# badgeSchem.net
KiCad netlist of a schematic drawn in EAGLE
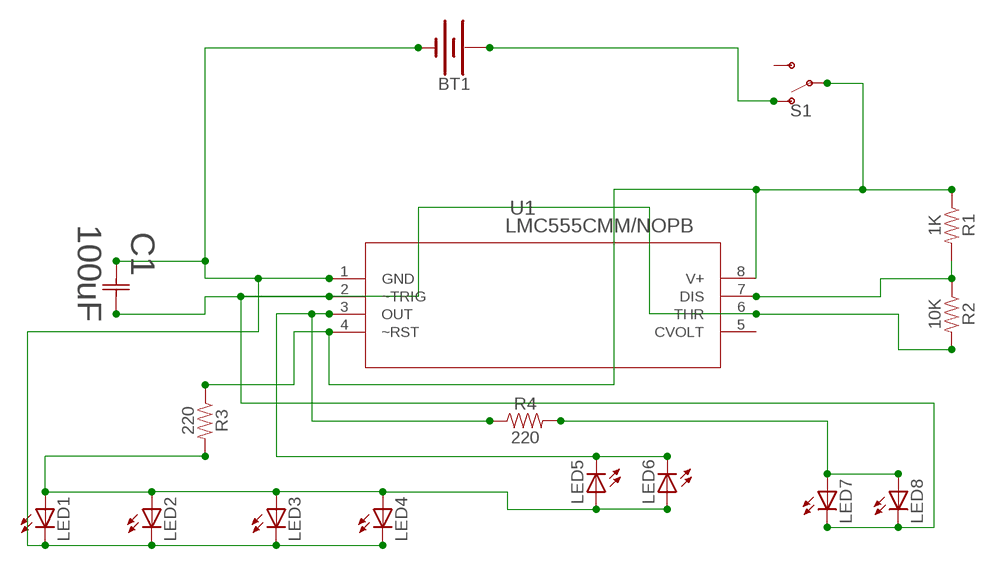
[diagram p0: schematic, sheet 1]

(export (version "E")
  (design (tool "Eeschema 10.0.6"))
  (components
    (comp (ref "BT1")
      (value "BATTERY-12MM_PTH")
      (footprint "eagle-import:BATTCON_12MM_PTH")
      (libsource (lib "eagle-import") (part "BATTERY-12MM_PTH"))
    )
    (comp (ref "C1")
      (value "100uF")
      (footprint "eagle-import:CAP_2012-M")
      (fields (field (name "MANUFACTURER_PART_NUMBER") "C2012C0G1H103J060AA"))
      (libsource (lib "eagle-import") (part "C2012C0G1H103J060AACAP_2012-M"))
    )
    (comp (ref "LED1")
      (value "LEDSML0805")
      (footprint "eagle-import:SML0805")
      (libsource (lib "eagle-import") (part "LEDSML0805"))
    )
    (comp (ref "LED2")
      (value "LEDSML0805")
      (footprint "eagle-import:SML0805")
      (libsource (lib "eagle-import") (part "LEDSML0805"))
    )
    (comp (ref "LED3")
      (value "LEDSML0805")
      (footprint "eagle-import:SML0805")
      (libsource (lib "eagle-import") (part "LEDSML0805"))
    )
    (comp (ref "LED4")
      (value "LEDSML0805")
      (footprint "eagle-import:SML0805")
      (libsource (lib "eagle-import") (part "LEDSML0805"))
    )
    (comp (ref "LED5")
      (value "LEDSML0805")
      (footprint "eagle-import:SML0805")
      (libsource (lib "eagle-import") (part "LEDSML0805"))
    )
    (comp (ref "LED6")
      (value "LEDSML0805")
      (footprint "eagle-import:SML0805")
      (libsource (lib "eagle-import") (part "LEDSML0805"))
    )
    (comp (ref "LED7")
      (value "LEDSML0805")
      (footprint "eagle-import:SML0805")
      (libsource (lib "eagle-import") (part "LEDSML0805"))
    )
    (comp (ref "LED8")
      (value "LEDSML0805")
      (footprint "eagle-import:SML0805")
      (libsource (lib "eagle-import") (part "LEDSML0805"))
    )
    (comp (ref "R1")
      (value "1K")
      (footprint "eagle-import:0805")
      (libsource (lib "eagle-import") (part "0.3OHM-0805-1/8W-1%"))
    )
    (comp (ref "R2")
      (value "10K")
      (footprint "eagle-import:0805")
      (libsource (lib "eagle-import") (part "0.3OHM-0805-1/8W-1%"))
    )
    (comp (ref "R3")
      (value "220")
      (footprint "eagle-import:0805")
      (libsource (lib "eagle-import") (part "0.3OHM-0805-1/8W-1%"))
    )
    (comp (ref "R4")
      (value "220")
      (footprint "eagle-import:0805")
      (libsource (lib "eagle-import") (part "0.3OHM-0805-1/8W-1%"))
    )
    (comp (ref "S1")
      (value "SWITCH-SPDT-SMD-RIGHT-ANGLE")
      (footprint "eagle-import:SWITCH_SPST_SMD_A")
      (libsource (lib "eagle-import") (part "SWITCH-SPDT-SMD-RIGHT-ANGLE"))
    )
    (comp (ref "U1")
      (value "LMC555CMM/NOPB")
      (footprint "eagle-import:MUA08A")
      (fields (field (name "MANUFACTURER_PART_NUMBER") "LMC555CMMNOPB"))
      (libsource (lib "eagle-import") (part "LMC555CMM/NOPB"))
    )
  )
  (nets
    (net (code "1") (name "Net-(BT1-+)") (class "Default")
      (node (ref "BT1") (pin "VCC@1") (pinfunction "+_VCC@1") (pintype "power_in"))
      (node (ref "S1") (pin "1") (pinfunction "O_1") (pintype "passive"))
    )
    (net (code "2") (name "Net-(BT1--)") (class "Default")
      (node (ref "BT1") (pin "GND") (pinfunction "-_GND") (pintype "power_in"))
      (node (ref "C1") (pin "1") (pinfunction "11_1") (pintype "passive"))
      (node (ref "LED1") (pin "C") (pinfunction "C_C") (pintype "passive"))
      (node (ref "LED2") (pin "C") (pinfunction "C_C") (pintype "passive"))
      (node (ref "LED3") (pin "C") (pinfunction "C_C") (pintype "passive"))
      (node (ref "LED4") (pin "C") (pinfunction "C_C") (pintype "passive"))
      (node (ref "U1") (pin "1") (pinfunction "GND_1") (pintype "power_in"))
    )
    (net (code "3") (name "Net-(C1-22)") (class "Default")
      (node (ref "C1") (pin "2") (pinfunction "22_2") (pintype "passive"))
      (node (ref "LED7") (pin "C") (pinfunction "C_C") (pintype "passive"))
      (node (ref "LED8") (pin "C") (pinfunction "C_C") (pintype "passive"))
      (node (ref "R2") (pin "2") (pinfunction "2_2") (pintype "passive"))
      (node (ref "U1") (pin "2") (pinfunction "~{TRIG}_2") (pintype "input"))
      (node (ref "U1") (pin "6") (pinfunction "THR_6") (pintype "input"))
    )
    (net (code "4") (name "Net-(LED1-PadA)") (class "Default")
      (node (ref "LED1") (pin "A") (pinfunction "A_A") (pintype "passive"))
      (node (ref "LED2") (pin "A") (pinfunction "A_A") (pintype "passive"))
      (node (ref "LED3") (pin "A") (pinfunction "A_A") (pintype "passive"))
      (node (ref "LED4") (pin "A") (pinfunction "A_A") (pintype "passive"))
      (node (ref "LED5") (pin "A") (pinfunction "A_A") (pintype "passive"))
      (node (ref "LED6") (pin "A") (pinfunction "A_A") (pintype "passive"))
      (node (ref "R3") (pin "2") (pinfunction "2_2") (pintype "passive"))
    )
    (net (code "5") (name "Net-(LED7-PadA)") (class "Default")
      (node (ref "LED7") (pin "A") (pinfunction "A_A") (pintype "passive"))
      (node (ref "LED8") (pin "A") (pinfunction "A_A") (pintype "passive"))
      (node (ref "R4") (pin "2") (pinfunction "2_2") (pintype "passive"))
    )
    (net (code "6") (name "Net-(S1-P)") (class "Default")
      (node (ref "R1") (pin "1") (pinfunction "1_1") (pintype "passive"))
      (node (ref "R3") (pin "1") (pinfunction "1_1") (pintype "passive"))
      (node (ref "S1") (pin "2") (pinfunction "P_2") (pintype "passive"))
      (node (ref "U1") (pin "4") (pinfunction "~{RST}_4") (pintype "input"))
      (node (ref "U1") (pin "8") (pinfunction "V+_8") (pintype "power_in"))
    )
    (net (code "7") (name "Net-(U1-DIS)") (class "Default")
      (node (ref "R1") (pin "2") (pinfunction "2_2") (pintype "passive"))
      (node (ref "R2") (pin "1") (pinfunction "1_1") (pintype "passive"))
      (node (ref "U1") (pin "7") (pinfunction "DIS_7") (pintype "passive"))
    )
    (net (code "8") (name "Net-(U1-OUT)") (class "Default")
      (node (ref "LED5") (pin "C") (pinfunction "C_C") (pintype "passive"))
      (node (ref "LED6") (pin "C") (pinfunction "C_C") (pintype "passive"))
      (node (ref "R4") (pin "1") (pinfunction "1_1") (pintype "passive"))
      (node (ref "U1") (pin "3") (pinfunction "OUT_3") (pintype "output"))
    )
    (net (code "9") (name "unconnected-(S1-S-Pad3)") (class "Default")
      (node (ref "S1") (pin "3") (pinfunction "S_3") (pintype "passive"))
    )
    (net (code "10") (name "unconnected-(U1-CVOLT-Pad5)") (class "Default")
      (node (ref "U1") (pin "5") (pinfunction "CVOLT_5") (pintype "passive"))
    )
  )
)
